# RTI-Dome-Shutter.net
KiCad netlist of a schematic drawn in EAGLE
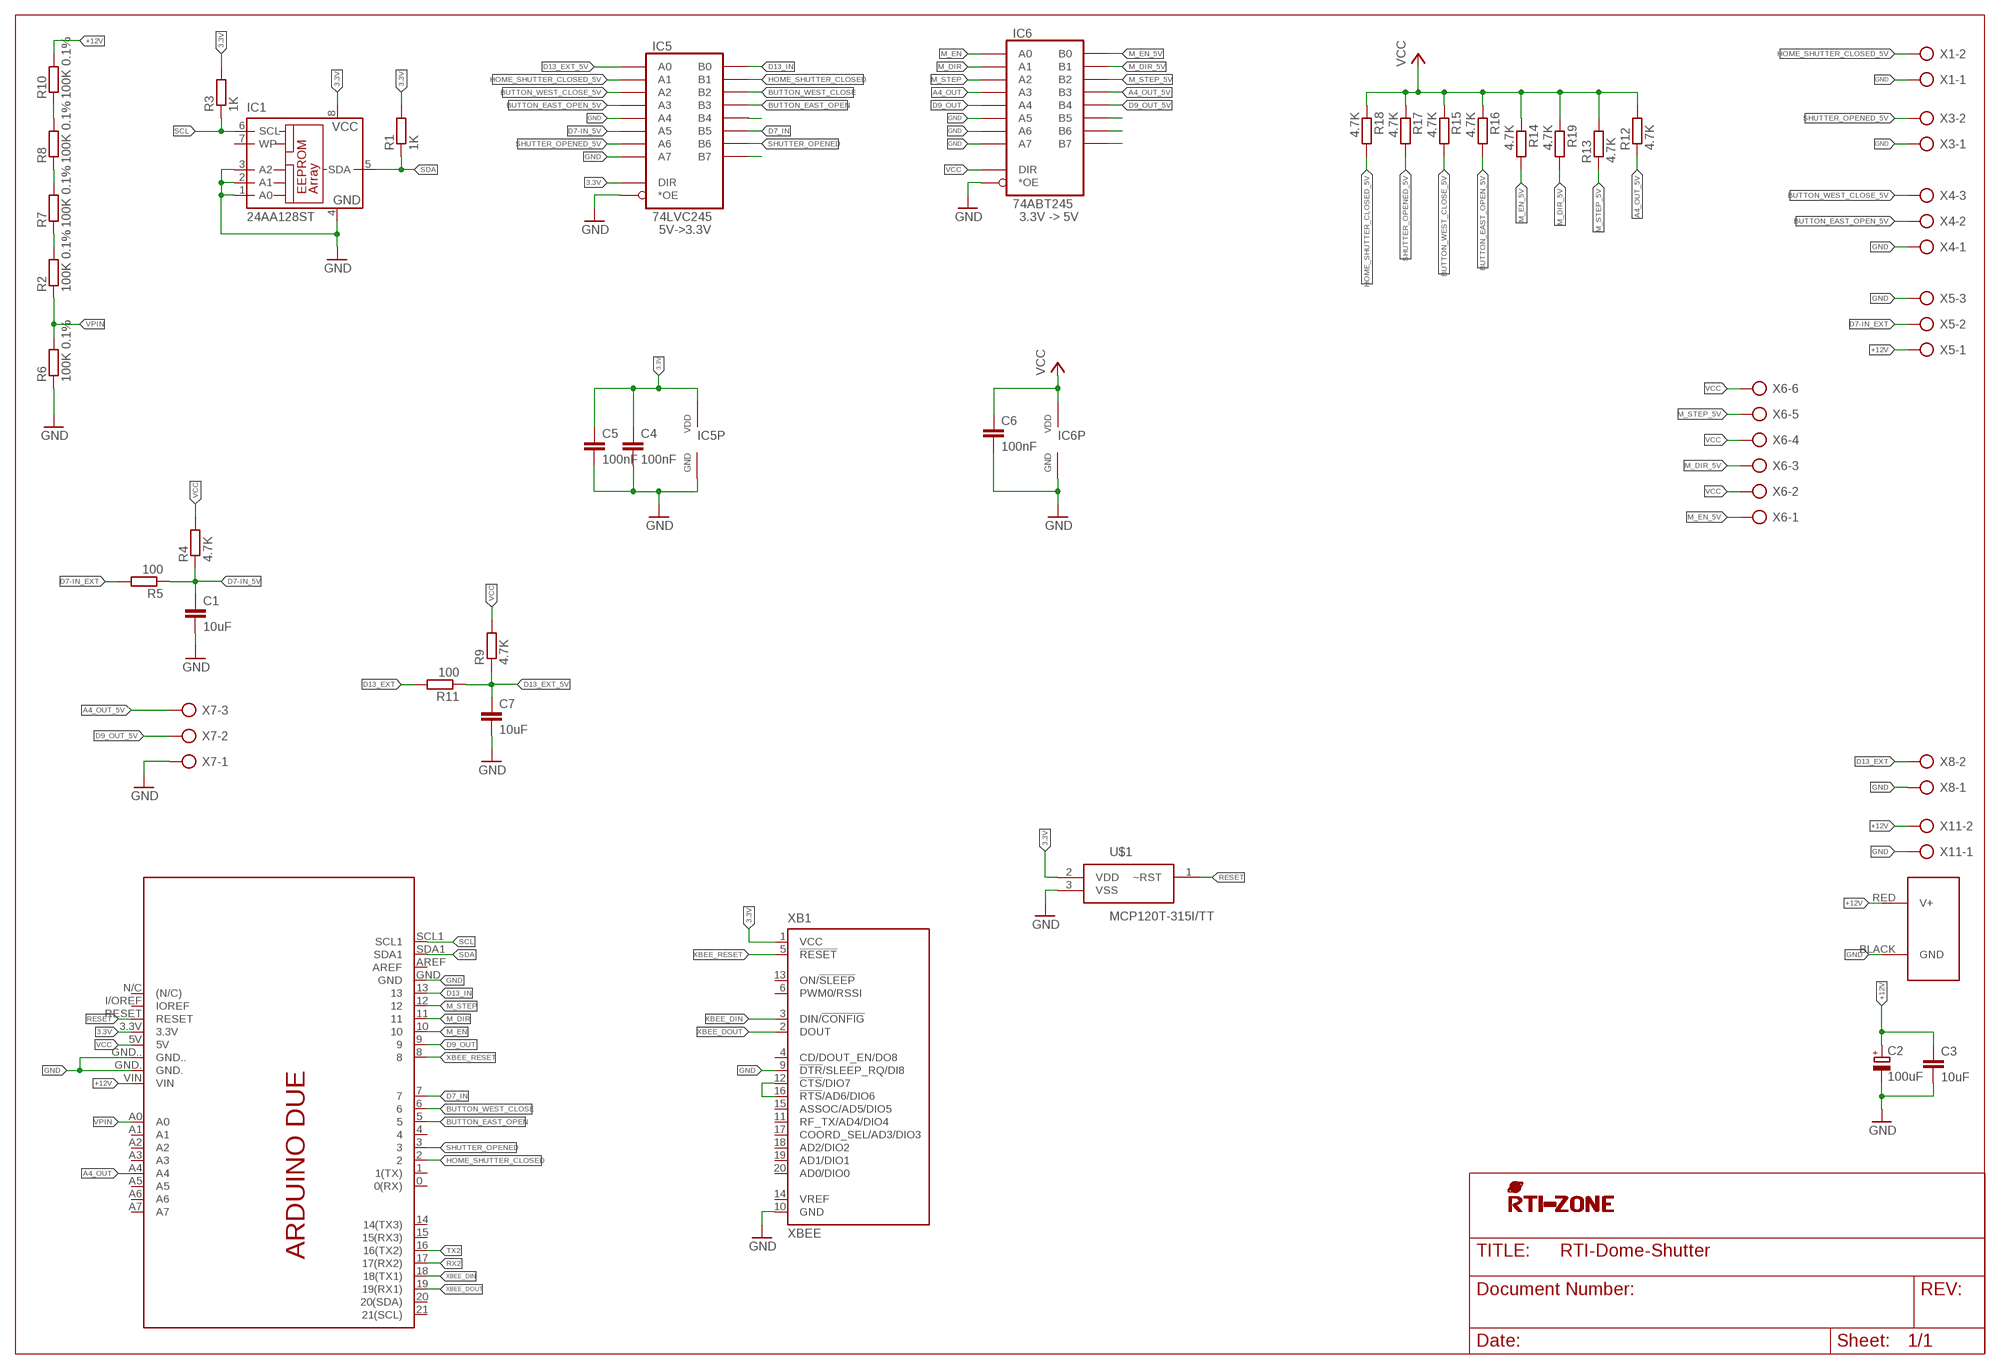
[diagram p0: schematic, sheet 1]

(export (version "E")
  (design (tool "Eeschema 10.0.6"))
  (components
    (comp (ref "C1")
      (value "10uF")
      (footprint "eagle-import:C0805")
      (libsource (lib "eagle-import") (part "C-EU'0805'"))
    )
    (comp (ref "C2")
      (value "100uF")
      (footprint "eagle-import:UD-10X10_NICHICON")
      (libsource (lib "eagle-import") (part "CPOL-EU"))
    )
    (comp (ref "C3")
      (value "10uF")
      (footprint "eagle-import:C0805")
      (libsource (lib "eagle-import") (part "C-EU'0805'"))
    )
    (comp (ref "C4")
      (value "100nF")
      (footprint "eagle-import:C0805")
      (libsource (lib "eagle-import") (part "C-EU'0805'"))
    )
    (comp (ref "C5")
      (value "100nF")
      (footprint "eagle-import:C0805")
      (libsource (lib "eagle-import") (part "C-EU'0805'"))
    )
    (comp (ref "C6")
      (value "100nF")
      (footprint "eagle-import:C0805")
      (libsource (lib "eagle-import") (part "C-EU'0805'"))
    )
    (comp (ref "C7")
      (value "10uF")
      (footprint "eagle-import:C0805")
      (libsource (lib "eagle-import") (part "C-EU'0805'"))
    )
    (comp (ref "IC1")
      (value "24AA128ST")
      (footprint "eagle-import:TSSOP8")
      (fields (field (name "MF") "MICROCHIP") (field (name "MPN") "24AA128-I/ST"))
      (libsource (lib "eagle-import") (part "24STAA128"))
    )
    (comp (ref "IC5")
      (value "74LVC245")
      (footprint "eagle-import:TSSOP20")
      (libsource (lib "eagle-import") (part "74245LVC"))
    )
    (comp (ref "IC6")
      (value "74ABT245")
      (footprint "eagle-import:TSSOP20")
      (libsource (lib "eagle-import") (part "74245ABT"))
    )
    (comp (ref "J1")
      (value "POWERPOLE_POWER45A")
      (footprint "eagle-import:POWERPOLE_PAIR_45A")
      (libsource (lib "eagle-import") (part "POWERPOLE_POWER45A"))
    )
    (comp (ref "PCB1")
      (value "ARDUINO_DUE_SHIELD_SHORT")
      (footprint "eagle-import:ARDUINO_DUE_SHIELD_SHORT")
      (libsource (lib "eagle-import") (part "ARDUINO_DUE_SHIELD_SHORT"))
    )
    (comp (ref "R1")
      (value "1K")
      (footprint "eagle-import:R0805")
      (libsource (lib "eagle-import") (part "R-EU'0805'"))
    )
    (comp (ref "R2")
      (value "100K 0.1%")
      (footprint "eagle-import:R0805")
      (libsource (lib "eagle-import") (part "R-EU'0805'"))
    )
    (comp (ref "R3")
      (value "1K")
      (footprint "eagle-import:R0805")
      (libsource (lib "eagle-import") (part "R-EU'0805'"))
    )
    (comp (ref "R4")
      (value "4.7K")
      (footprint "eagle-import:R0805")
      (libsource (lib "eagle-import") (part "R-EU'0805'"))
    )
    (comp (ref "R5")
      (value "100")
      (footprint "eagle-import:R0805")
      (libsource (lib "eagle-import") (part "R-EU'0805'"))
    )
    (comp (ref "R6")
      (value "100K 0.1%")
      (footprint "eagle-import:R0805")
      (libsource (lib "eagle-import") (part "R-EU'0805'"))
    )
    (comp (ref "R7")
      (value "100K 0.1%")
      (footprint "eagle-import:R0805")
      (libsource (lib "eagle-import") (part "R-EU'0805'"))
    )
    (comp (ref "R8")
      (value "100K 0.1%")
      (footprint "eagle-import:R0805")
      (libsource (lib "eagle-import") (part "R-EU'0805'"))
    )
    (comp (ref "R9")
      (value "4.7K")
      (footprint "eagle-import:R0805")
      (libsource (lib "eagle-import") (part "R-EU'0805'"))
    )
    (comp (ref "R10")
      (value "100K 0.1%")
      (footprint "eagle-import:R0805")
      (libsource (lib "eagle-import") (part "R-EU'0805'"))
    )
    (comp (ref "R11")
      (value "100")
      (footprint "eagle-import:R0805")
      (libsource (lib "eagle-import") (part "R-EU'0805'"))
    )
    (comp (ref "R12")
      (value "4.7K")
      (footprint "eagle-import:R0805")
      (libsource (lib "eagle-import") (part "R-EU'0805'"))
    )
    (comp (ref "R13")
      (value "4.7K")
      (footprint "eagle-import:R0805")
      (libsource (lib "eagle-import") (part "R-EU'0805'"))
    )
    (comp (ref "R14")
      (value "4.7K")
      (footprint "eagle-import:R0805")
      (libsource (lib "eagle-import") (part "R-EU'0805'"))
    )
    (comp (ref "R15")
      (value "4.7K")
      (footprint "eagle-import:R0805")
      (libsource (lib "eagle-import") (part "R-EU'0805'"))
    )
    (comp (ref "R16")
      (value "4.7K")
      (footprint "eagle-import:R0805")
      (libsource (lib "eagle-import") (part "R-EU'0805'"))
    )
    (comp (ref "R17")
      (value "4.7K")
      (footprint "eagle-import:R0805")
      (libsource (lib "eagle-import") (part "R-EU'0805'"))
    )
    (comp (ref "R18")
      (value "4.7K")
      (footprint "eagle-import:R0805")
      (libsource (lib "eagle-import") (part "R-EU'0805'"))
    )
    (comp (ref "R19")
      (value "4.7K")
      (footprint "eagle-import:R0805")
      (libsource (lib "eagle-import") (part "R-EU'0805'"))
    )
    (comp (ref "U$1")
      (value "MCP120T-315I/TT")
      (footprint "eagle-import:SOT95P237X112-3N")
      (fields (field (name "MOUSER_PART_NUMBER") "579-MCP120T-315I/TT"))
      (libsource (lib "eagle-import") (part "MCP120T"))
    )
    (comp (ref "U$4")
      (value "RTI-LOGO_BIG")
      (footprint "eagle-import:LOGO_BIG")
      (libsource (lib "eagle-import") (part "RTI-LOGO_BIG"))
    )
    (comp (ref "X1")
      (value "AK500/2")
      (footprint "eagle-import:AK500_2")
      (libsource (lib "eagle-import") (part "AK500/2"))
    )
    (comp (ref "X3")
      (value "AK500/2")
      (footprint "eagle-import:AK500_2")
      (libsource (lib "eagle-import") (part "AK500/2"))
    )
    (comp (ref "X4")
      (value "AK500/3")
      (footprint "eagle-import:AK500_3")
      (libsource (lib "eagle-import") (part "AK500/3"))
    )
    (comp (ref "X5")
      (value "AK500/3")
      (footprint "eagle-import:AK500_3")
      (libsource (lib "eagle-import") (part "AK500/3"))
    )
    (comp (ref "X6")
      (value "AK500/6")
      (footprint "eagle-import:AK500_6")
      (libsource (lib "eagle-import") (part "AK500/6"))
    )
    (comp (ref "X7")
      (value "AK500/3")
      (footprint "eagle-import:AK500_3")
      (libsource (lib "eagle-import") (part "AK500/3"))
    )
    (comp (ref "X8")
      (value "AK500/2")
      (footprint "eagle-import:AK500_2")
      (libsource (lib "eagle-import") (part "AK500/2"))
    )
    (comp (ref "X11")
      (value "AK500/2")
      (footprint "eagle-import:AK500_2")
      (libsource (lib "eagle-import") (part "AK500/2"))
    )
    (comp (ref "XB1")
      (value "XBEE")
      (footprint "eagle-import:XBEE")
      (fields (field (name "MPN") "XBP24-Z7UIT-004"))
      (libsource (lib "eagle-import") (part "XBEE"))
    )
  )
  (nets
    (net (code "1") (name "+12V") (class "Default")
      (node (ref "C2") (pin "+") (pinfunction "+_+") (pintype "passive"))
      (node (ref "C3") (pin "1") (pinfunction "1_1") (pintype "passive"))
      (node (ref "J1") (pin "RED") (pinfunction "V+_RED") (pintype "power_in"))
      (node (ref "PCB1") (pin "VIN") (pinfunction "VIN_VIN") (pintype "bidirectional"))
      (node (ref "R10") (pin "2") (pinfunction "2_2") (pintype "passive"))
      (node (ref "X11") (pin "2") (pinfunction "KL_2") (pintype "passive"))
      (node (ref "X5") (pin "1") (pinfunction "KL_1") (pintype "passive"))
    )
    (net (code "2") (name "3.3V") (class "Default")
      (node (ref "C4") (pin "1") (pinfunction "1_1") (pintype "passive"))
      (node (ref "C5") (pin "1") (pinfunction "1_1") (pintype "passive"))
      (node (ref "IC1") (pin "8") (pinfunction "VCC_8") (pintype "power_in"))
      (node (ref "IC5") (pin "P$1") (pinfunction "DIR_P$1") (pintype "input"))
      (node (ref "IC5") (pin "P$20") (pinfunction "VDD_P$20") (pintype "power_in"))
      (node (ref "PCB1") (pin "3.3V") (pinfunction "3.3V_3.3V") (pintype "bidirectional"))
      (node (ref "R1") (pin "2") (pinfunction "2_2") (pintype "passive"))
      (node (ref "R3") (pin "2") (pinfunction "2_2") (pintype "passive"))
      (node (ref "U$1") (pin "2") (pinfunction "VDD_2") (pintype "bidirectional"))
      (node (ref "XB1") (pin "1") (pinfunction "VCC_1") (pintype "power_in"))
    )
    (net (code "3") (name "A4_OUT") (class "Default")
      (node (ref "IC6") (pin "P$5") (pinfunction "A3_P$5") (pintype "bidirectional"))
      (node (ref "PCB1") (pin "A4") (pinfunction "A4_A4") (pintype "bidirectional"))
    )
    (net (code "4") (name "A4_OUT_5V") (class "Default")
      (node (ref "IC6") (pin "P$15") (pinfunction "B3_P$15") (pintype "bidirectional"))
      (node (ref "R12") (pin "1") (pinfunction "1_1") (pintype "passive"))
      (node (ref "X7") (pin "3") (pinfunction "KL_3") (pintype "passive"))
    )
    (net (code "5") (name "BUTTON_EAST_OPEN") (class "Default")
      (node (ref "IC5") (pin "P$15") (pinfunction "B3_P$15") (pintype "bidirectional"))
      (node (ref "PCB1") (pin "5") (pinfunction "5_5") (pintype "bidirectional"))
    )
    (net (code "6") (name "BUTTON_EAST_OPEN_5V") (class "Default")
      (node (ref "IC5") (pin "P$5") (pinfunction "A3_P$5") (pintype "bidirectional"))
      (node (ref "R16") (pin "2") (pinfunction "2_2") (pintype "passive"))
      (node (ref "X4") (pin "2") (pinfunction "KL_2") (pintype "passive"))
    )
    (net (code "7") (name "BUTTON_WEST_CLOSE") (class "Default")
      (node (ref "IC5") (pin "P$16") (pinfunction "B2_P$16") (pintype "bidirectional"))
      (node (ref "PCB1") (pin "6") (pinfunction "6_6") (pintype "bidirectional"))
    )
    (net (code "8") (name "BUTTON_WEST_CLOSE_5V") (class "Default")
      (node (ref "IC5") (pin "P$4") (pinfunction "A2_P$4") (pintype "bidirectional"))
      (node (ref "R15") (pin "2") (pinfunction "2_2") (pintype "passive"))
      (node (ref "X4") (pin "3") (pinfunction "KL_3") (pintype "passive"))
    )
    (net (code "9") (name "D7-IN_5V") (class "Default")
      (node (ref "C1") (pin "1") (pinfunction "1_1") (pintype "passive"))
      (node (ref "IC5") (pin "P$7") (pinfunction "A5_P$7") (pintype "bidirectional"))
      (node (ref "R4") (pin "1") (pinfunction "1_1") (pintype "passive"))
      (node (ref "R5") (pin "1") (pinfunction "1_1") (pintype "passive"))
    )
    (net (code "10") (name "D7-IN_EXT") (class "Default")
      (node (ref "R5") (pin "2") (pinfunction "2_2") (pintype "passive"))
      (node (ref "X5") (pin "2") (pinfunction "KL_2") (pintype "passive"))
    )
    (net (code "11") (name "D7_IN") (class "Default")
      (node (ref "IC5") (pin "P$13") (pinfunction "B5_P$13") (pintype "bidirectional"))
      (node (ref "PCB1") (pin "7") (pinfunction "7_7") (pintype "bidirectional"))
    )
    (net (code "12") (name "D9_OUT") (class "Default")
      (node (ref "IC6") (pin "P$6") (pinfunction "A4_P$6") (pintype "bidirectional"))
      (node (ref "PCB1") (pin "9") (pinfunction "9_9") (pintype "bidirectional"))
    )
    (net (code "13") (name "D9_OUT_5V") (class "Default")
      (node (ref "IC6") (pin "P$14") (pinfunction "B4_P$14") (pintype "bidirectional"))
      (node (ref "X7") (pin "2") (pinfunction "KL_2") (pintype "passive"))
    )
    (net (code "14") (name "D13_EXT") (class "Default")
      (node (ref "R11") (pin "2") (pinfunction "2_2") (pintype "passive"))
      (node (ref "X8") (pin "2") (pinfunction "KL_2") (pintype "passive"))
    )
    (net (code "15") (name "D13_EXT_5V") (class "Default")
      (node (ref "C7") (pin "1") (pinfunction "1_1") (pintype "passive"))
      (node (ref "IC5") (pin "P$2") (pinfunction "A0_P$2") (pintype "bidirectional"))
      (node (ref "R11") (pin "1") (pinfunction "1_1") (pintype "passive"))
      (node (ref "R9") (pin "1") (pinfunction "1_1") (pintype "passive"))
    )
    (net (code "16") (name "D13_IN") (class "Default")
      (node (ref "IC5") (pin "P$18") (pinfunction "B0_P$18") (pintype "bidirectional"))
      (node (ref "PCB1") (pin "13") (pinfunction "13_13") (pintype "bidirectional"))
    )
    (net (code "17") (name "GND") (class "Default")
      (node (ref "C1") (pin "2") (pinfunction "2_2") (pintype "passive"))
      (node (ref "C2") (pin "-") (pinfunction "-_-") (pintype "passive"))
      (node (ref "C3") (pin "2") (pinfunction "2_2") (pintype "passive"))
      (node (ref "C4") (pin "2") (pinfunction "2_2") (pintype "passive"))
      (node (ref "C5") (pin "2") (pinfunction "2_2") (pintype "passive"))
      (node (ref "C6") (pin "2") (pinfunction "2_2") (pintype "passive"))
      (node (ref "C7") (pin "2") (pinfunction "2_2") (pintype "passive"))
      (node (ref "IC1") (pin "1") (pinfunction "A0_1") (pintype "input"))
      (node (ref "IC1") (pin "2") (pinfunction "A1_2") (pintype "input"))
      (node (ref "IC1") (pin "3") (pinfunction "A2_3") (pintype "input"))
      (node (ref "IC1") (pin "4") (pinfunction "GND_4") (pintype "power_in"))
      (node (ref "IC5") (pin "P$10") (pinfunction "GND_P$10") (pintype "power_in"))
      (node (ref "IC5") (pin "P$19") (pinfunction "*OE_P$19") (pintype "input"))
      (node (ref "IC5") (pin "P$6") (pinfunction "A4_P$6") (pintype "bidirectional"))
      (node (ref "IC5") (pin "P$9") (pinfunction "A7_P$9") (pintype "bidirectional"))
      (node (ref "IC6") (pin "P$10") (pinfunction "GND_P$10") (pintype "power_in"))
      (node (ref "IC6") (pin "P$19") (pinfunction "*OE_P$19") (pintype "input"))
      (node (ref "IC6") (pin "P$7") (pinfunction "A5_P$7") (pintype "bidirectional"))
      (node (ref "IC6") (pin "P$8") (pinfunction "A6_P$8") (pintype "bidirectional"))
      (node (ref "IC6") (pin "P$9") (pinfunction "A7_P$9") (pintype "bidirectional"))
      (node (ref "J1") (pin "BLACK") (pinfunction "GND_BLACK") (pintype "power_in"))
      (node (ref "PCB1") (pin "GND") (pinfunction "GND_GND") (pintype "bidirectional"))
      (node (ref "PCB1") (pin "GND.") (pinfunction "GND._GND.") (pintype "bidirectional"))
      (node (ref "PCB1") (pin "GND..") (pinfunction "GND.._GND..") (pintype "bidirectional"))
      (node (ref "R6") (pin "1") (pinfunction "1_1") (pintype "passive"))
      (node (ref "U$1") (pin "3") (pinfunction "VSS_3") (pintype "bidirectional"))
      (node (ref "X1") (pin "1") (pinfunction "KL_1") (pintype "passive"))
      (node (ref "X11") (pin "1") (pinfunction "KL_1") (pintype "passive"))
      (node (ref "X3") (pin "1") (pinfunction "KL_1") (pintype "passive"))
      (node (ref "X4") (pin "1") (pinfunction "KL_1") (pintype "passive"))
      (node (ref "X5") (pin "3") (pinfunction "KL_3") (pintype "passive"))
      (node (ref "X7") (pin "1") (pinfunction "KL_1") (pintype "passive"))
      (node (ref "X8") (pin "1") (pinfunction "KL_1") (pintype "passive"))
      (node (ref "XB1") (pin "10") (pinfunction "GND_10") (pintype "power_in"))
      (node (ref "XB1") (pin "9") (pinfunction "~{DTR}/SLEEP_RQ/DI8_9") (pintype "bidirectional"))
    )
    (net (code "18") (name "HOME_SHUTTER_CLOSED") (class "Default")
      (node (ref "IC5") (pin "P$17") (pinfunction "B1_P$17") (pintype "bidirectional"))
      (node (ref "PCB1") (pin "2") (pinfunction "2_2") (pintype "bidirectional"))
    )
    (net (code "19") (name "HOME_SHUTTER_CLOSED_5V") (class "Default")
      (node (ref "IC5") (pin "P$3") (pinfunction "A1_P$3") (pintype "bidirectional"))
      (node (ref "R18") (pin "2") (pinfunction "2_2") (pintype "passive"))
      (node (ref "X1") (pin "2") (pinfunction "KL_2") (pintype "passive"))
    )
    (net (code "20") (name "M_DIR") (class "Default")
      (node (ref "IC6") (pin "P$3") (pinfunction "A1_P$3") (pintype "bidirectional"))
      (node (ref "PCB1") (pin "11") (pinfunction "11_11") (pintype "bidirectional"))
    )
    (net (code "21") (name "M_DIR_5V") (class "Default")
      (node (ref "IC6") (pin "P$17") (pinfunction "B1_P$17") (pintype "bidirectional"))
      (node (ref "R19") (pin "2") (pinfunction "2_2") (pintype "passive"))
      (node (ref "X6") (pin "3") (pinfunction "KL_3") (pintype "passive"))
    )
    (net (code "22") (name "M_EN") (class "Default")
      (node (ref "IC6") (pin "P$2") (pinfunction "A0_P$2") (pintype "bidirectional"))
      (node (ref "PCB1") (pin "10") (pinfunction "10_10") (pintype "bidirectional"))
    )
    (net (code "23") (name "M_EN_5V") (class "Default")
      (node (ref "IC6") (pin "P$18") (pinfunction "B0_P$18") (pintype "bidirectional"))
      (node (ref "R14") (pin "2") (pinfunction "2_2") (pintype "passive"))
      (node (ref "X6") (pin "1") (pinfunction "KL_1") (pintype "passive"))
    )
    (net (code "24") (name "M_STEP") (class "Default")
      (node (ref "IC6") (pin "P$4") (pinfunction "A2_P$4") (pintype "bidirectional"))
      (node (ref "PCB1") (pin "12") (pinfunction "12_12") (pintype "bidirectional"))
    )
    (net (code "25") (name "M_STEP_5V") (class "Default")
      (node (ref "IC6") (pin "P$16") (pinfunction "B2_P$16") (pintype "bidirectional"))
      (node (ref "R13") (pin "1") (pinfunction "1_1") (pintype "passive"))
      (node (ref "X6") (pin "5") (pinfunction "KL_5") (pintype "passive"))
    )
    (net (code "26") (name "Net-(R2-Pad2)") (class "Default")
      (node (ref "R2") (pin "2") (pinfunction "2_2") (pintype "passive"))
      (node (ref "R7") (pin "1") (pinfunction "1_1") (pintype "passive"))
    )
    (net (code "27") (name "Net-(R7-Pad2)") (class "Default")
      (node (ref "R7") (pin "2") (pinfunction "2_2") (pintype "passive"))
      (node (ref "R8") (pin "1") (pinfunction "1_1") (pintype "passive"))
    )
    (net (code "28") (name "Net-(R10-Pad1)") (class "Default")
      (node (ref "R10") (pin "1") (pinfunction "1_1") (pintype "passive"))
      (node (ref "R8") (pin "2") (pinfunction "2_2") (pintype "passive"))
    )
    (net (code "29") (name "Net-(XB1-~{CTS}{slash}DIO7)") (class "Default")
      (node (ref "XB1") (pin "12") (pinfunction "~{CTS}/DIO7_12") (pintype "bidirectional"))
      (node (ref "XB1") (pin "16") (pinfunction "~{RTS}/AD6/DIO6_16") (pintype "bidirectional"))
    )
    (net (code "30") (name "RESET") (class "Default")
      (node (ref "PCB1") (pin "RESET") (pinfunction "RESET_RESET") (pintype "bidirectional"))
      (node (ref "U$1") (pin "1") (pinfunction "~{RST}_1") (pintype "bidirectional"))
    )
    (net (code "31") (name "RX2") (class "Default")
      (node (ref "PCB1") (pin "17") (pinfunction "17(RX2)_17") (pintype "bidirectional"))
    )
    (net (code "32") (name "SCL") (class "Default")
      (node (ref "IC1") (pin "6") (pinfunction "SCL_6") (pintype "input"))
      (node (ref "PCB1") (pin "SCL1") (pinfunction "SCL1_SCL1") (pintype "bidirectional"))
      (node (ref "R3") (pin "1") (pinfunction "1_1") (pintype "passive"))
    )
    (net (code "33") (name "SDA") (class "Default")
      (node (ref "IC1") (pin "5") (pinfunction "SDA_5") (pintype "bidirectional"))
      (node (ref "PCB1") (pin "SDA1") (pinfunction "SDA1_SDA1") (pintype "bidirectional"))
      (node (ref "R1") (pin "1") (pinfunction "1_1") (pintype "passive"))
    )
    (net (code "34") (name "SHUTTER_OPENED") (class "Default")
      (node (ref "IC5") (pin "P$12") (pinfunction "B6_P$12") (pintype "bidirectional"))
      (node (ref "PCB1") (pin "3") (pinfunction "3_3") (pintype "bidirectional"))
    )
    (net (code "35") (name "SHUTTER_OPENED_5V") (class "Default")
      (node (ref "IC5") (pin "P$8") (pinfunction "A6_P$8") (pintype "bidirectional"))
      (node (ref "R17") (pin "2") (pinfunction "2_2") (pintype "passive"))
      (node (ref "X3") (pin "2") (pinfunction "KL_2") (pintype "passive"))
    )
    (net (code "36") (name "TX2") (class "Default")
      (node (ref "PCB1") (pin "16") (pinfunction "16(TX2)_16") (pintype "bidirectional"))
    )
    (net (code "37") (name "VCC") (class "Default")
      (node (ref "C6") (pin "1") (pinfunction "1_1") (pintype "passive"))
      (node (ref "IC6") (pin "P$1") (pinfunction "DIR_P$1") (pintype "input"))
      (node (ref "IC6") (pin "P$20") (pinfunction "VDD_P$20") (pintype "power_in"))
      (node (ref "PCB1") (pin "5V") (pinfunction "5V_5V") (pintype "bidirectional"))
      (node (ref "R12") (pin "2") (pinfunction "2_2") (pintype "passive"))
      (node (ref "R13") (pin "2") (pinfunction "2_2") (pintype "passive"))
      (node (ref "R14") (pin "1") (pinfunction "1_1") (pintype "passive"))
      (node (ref "R15") (pin "1") (pinfunction "1_1") (pintype "passive"))
      (node (ref "R16") (pin "1") (pinfunction "1_1") (pintype "passive"))
      (node (ref "R17") (pin "1") (pinfunction "1_1") (pintype "passive"))
      (node (ref "R18") (pin "1") (pinfunction "1_1") (pintype "passive"))
      (node (ref "R19") (pin "1") (pinfunction "1_1") (pintype "passive"))
      (node (ref "R4") (pin "2") (pinfunction "2_2") (pintype "passive"))
      (node (ref "R9") (pin "2") (pinfunction "2_2") (pintype "passive"))
      (node (ref "X6") (pin "2") (pinfunction "KL_2") (pintype "passive"))
      (node (ref "X6") (pin "4") (pinfunction "KL_4") (pintype "passive"))
      (node (ref "X6") (pin "6") (pinfunction "KL_6") (pintype "passive"))
    )
    (net (code "38") (name "VPIN") (class "Default")
      (node (ref "PCB1") (pin "A0") (pinfunction "A0_A0") (pintype "bidirectional"))
      (node (ref "R2") (pin "1") (pinfunction "1_1") (pintype "passive"))
      (node (ref "R6") (pin "2") (pinfunction "2_2") (pintype "passive"))
    )
    (net (code "39") (name "XBEE_DIN") (class "Default")
      (node (ref "PCB1") (pin "18") (pinfunction "18(TX1)_18") (pintype "bidirectional"))
      (node (ref "XB1") (pin "3") (pinfunction "DIN/~{CONFIG}_3") (pintype "input"))
    )
    (net (code "40") (name "XBEE_DOUT") (class "Default")
      (node (ref "PCB1") (pin "19") (pinfunction "19(RX1)_19") (pintype "bidirectional"))
      (node (ref "XB1") (pin "2") (pinfunction "DOUT_2") (pintype "output"))
    )
    (net (code "41") (name "XBEE_RESET") (class "Default")
      (node (ref "PCB1") (pin "8") (pinfunction "8_8") (pintype "bidirectional"))
      (node (ref "XB1") (pin "5") (pinfunction "~{RESET}_5") (pintype "input"))
    )
    (net (code "42") (name "unconnected-(IC1-WP-Pad7)") (class "Default")
      (node (ref "IC1") (pin "7") (pinfunction "WP_7") (pintype "input"))
    )
    (net (code "43") (name "unconnected-(IC5A-B4-PadP$14)") (class "Default")
      (node (ref "IC5") (pin "P$14") (pinfunction "B4_P$14") (pintype "bidirectional"))
    )
    (net (code "44") (name "unconnected-(IC5A-B7-PadP$11)") (class "Default")
      (node (ref "IC5") (pin "P$11") (pinfunction "B7_P$11") (pintype "bidirectional"))
    )
    (net (code "45") (name "unconnected-(IC6A-B5-PadP$13)") (class "Default")
      (node (ref "IC6") (pin "P$13") (pinfunction "B5_P$13") (pintype "bidirectional"))
    )
    (net (code "46") (name "unconnected-(IC6A-B6-PadP$12)") (class "Default")
      (node (ref "IC6") (pin "P$12") (pinfunction "B6_P$12") (pintype "bidirectional"))
    )
    (net (code "47") (name "unconnected-(IC6A-B7-PadP$11)") (class "Default")
      (node (ref "IC6") (pin "P$11") (pinfunction "B7_P$11") (pintype "bidirectional"))
    )
    (net (code "48") (name "unconnected-(PCB1-(N{slash}C)-PadN{slash}C)") (class "Default")
      (node (ref "PCB1") (pin "N/C") (pinfunction "(N/C)_N/C") (pintype "bidirectional"))
    )
    (net (code "49") (name "unconnected-(PCB1-0(RX)-Pad0)") (class "Default")
      (node (ref "PCB1") (pin "0") (pinfunction "0(RX)_0") (pintype "bidirectional"))
    )
    (net (code "50") (name "unconnected-(PCB1-1(TX)-Pad1)") (class "Default")
      (node (ref "PCB1") (pin "1") (pinfunction "1(TX)_1") (pintype "bidirectional"))
    )
    (net (code "51") (name "unconnected-(PCB1-14(TX3)-Pad14)") (class "Default")
      (node (ref "PCB1") (pin "14") (pinfunction "14(TX3)_14") (pintype "bidirectional"))
    )
    (net (code "52") (name "unconnected-(PCB1-15(RX3)-Pad15)") (class "Default")
      (node (ref "PCB1") (pin "15") (pinfunction "15(RX3)_15") (pintype "bidirectional"))
    )
    (net (code "53") (name "unconnected-(PCB1-20(SDA)-Pad20)") (class "Default")
      (node (ref "PCB1") (pin "20") (pinfunction "20(SDA)_20") (pintype "bidirectional"))
    )
    (net (code "54") (name "unconnected-(PCB1-21(SCL)-Pad21)") (class "Default")
      (node (ref "PCB1") (pin "21") (pinfunction "21(SCL)_21") (pintype "bidirectional"))
    )
    (net (code "55") (name "unconnected-(PCB1-IOREF-PadI{slash}OREF)") (class "Default")
      (node (ref "PCB1") (pin "I/OREF") (pinfunction "IOREF_I/OREF") (pintype "bidirectional"))
    )
    (net (code "56") (name "unconnected-(PCB1-Pad4)") (class "Default")
      (node (ref "PCB1") (pin "4") (pinfunction "4_4") (pintype "bidirectional"))
    )
    (net (code "57") (name "unconnected-(PCB1-PadA1)") (class "Default")
      (node (ref "PCB1") (pin "A1") (pinfunction "A1_A1") (pintype "bidirectional"))
    )
    (net (code "58") (name "unconnected-(PCB1-PadA2)") (class "Default")
      (node (ref "PCB1") (pin "A2") (pinfunction "A2_A2") (pintype "bidirectional"))
    )
    (net (code "59") (name "unconnected-(PCB1-PadA3)") (class "Default")
      (node (ref "PCB1") (pin "A3") (pinfunction "A3_A3") (pintype "bidirectional"))
    )
    (net (code "60") (name "unconnected-(PCB1-PadA5)") (class "Default")
      (node (ref "PCB1") (pin "A5") (pinfunction "A5_A5") (pintype "bidirectional"))
    )
    (net (code "61") (name "unconnected-(PCB1-PadA6)") (class "Default")
      (node (ref "PCB1") (pin "A6") (pinfunction "A6_A6") (pintype "bidirectional"))
    )
    (net (code "62") (name "unconnected-(PCB1-PadA7)") (class "Default")
      (node (ref "PCB1") (pin "A7") (pinfunction "A7_A7") (pintype "bidirectional"))
    )
    (net (code "63") (name "unconnected-(PCB1-PadAREF)") (class "Default")
      (node (ref "PCB1") (pin "AREF") (pinfunction "AREF_AREF") (pintype "bidirectional"))
    )
    (net (code "64") (name "unconnected-(XB1-AD0{slash}DIO0-Pad20)") (class "Default")
      (node (ref "XB1") (pin "20") (pinfunction "AD0/DIO0_20") (pintype "bidirectional"))
    )
    (net (code "65") (name "unconnected-(XB1-AD1{slash}DIO1-Pad19)") (class "Default")
      (node (ref "XB1") (pin "19") (pinfunction "AD1/DIO1_19") (pintype "bidirectional"))
    )
    (net (code "66") (name "unconnected-(XB1-AD2{slash}DIO2-Pad18)") (class "Default")
      (node (ref "XB1") (pin "18") (pinfunction "AD2/DIO2_18") (pintype "bidirectional"))
    )
    (net (code "67") (name "unconnected-(XB1-ASSOC{slash}AD5{slash}DIO5-Pad15)") (class "Default")
      (node (ref "XB1") (pin "15") (pinfunction "ASSOC/AD5/DIO5_15") (pintype "bidirectional"))
    )
    (net (code "68") (name "unconnected-(XB1-CD{slash}DOUT_EN{slash}DO8-Pad4)") (class "Default")
      (node (ref "XB1") (pin "4") (pinfunction "CD/DOUT_EN/DO8_4") (pintype "output"))
    )
    (net (code "69") (name "unconnected-(XB1-COORD_SEL{slash}AD3{slash}DIO3-Pad17)") (class "Default")
      (node (ref "XB1") (pin "17") (pinfunction "COORD_SEL/AD3/DIO3_17") (pintype "bidirectional"))
    )
    (net (code "70") (name "unconnected-(XB1-ON{slash}~{SLEEP}-Pad13)") (class "Default")
      (node (ref "XB1") (pin "13") (pinfunction "ON/~{SLEEP}_13") (pintype "output"))
    )
    (net (code "71") (name "unconnected-(XB1-PWM0{slash}RSSI-Pad6)") (class "Default")
      (node (ref "XB1") (pin "6") (pinfunction "PWM0/RSSI_6") (pintype "output"))
    )
    (net (code "72") (name "unconnected-(XB1-RF_TX{slash}AD4{slash}DIO4-Pad11)") (class "Default")
      (node (ref "XB1") (pin "11") (pinfunction "RF_TX/AD4/DIO4_11") (pintype "bidirectional"))
    )
    (net (code "73") (name "unconnected-(XB1-VREF-Pad14)") (class "Default")
      (node (ref "XB1") (pin "14") (pinfunction "VREF_14") (pintype "input"))
    )
  )
)
